# I2C-LLC_Mk_01.net
KiCad netlist of a schematic drawn in EAGLE
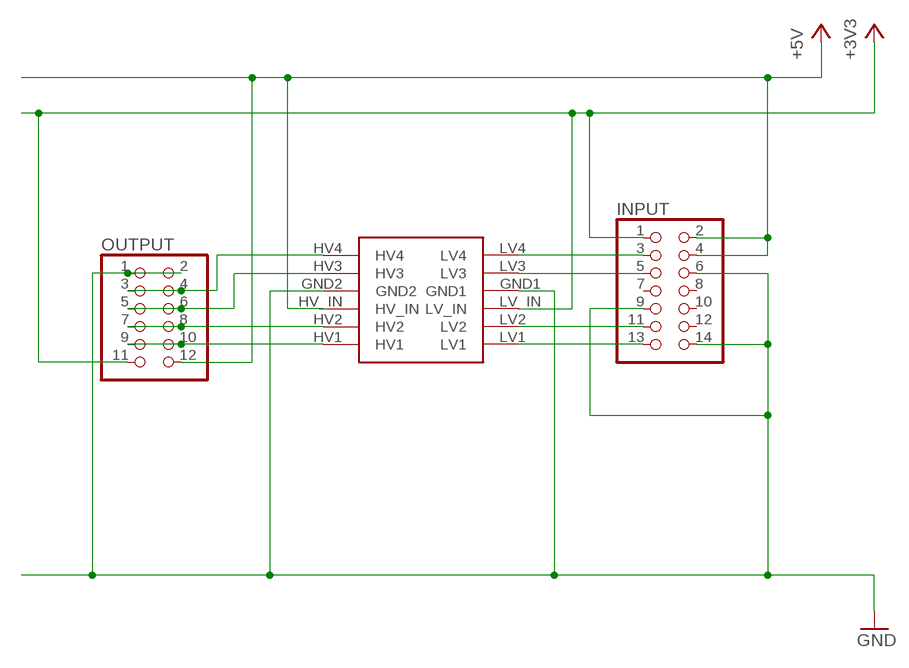
[diagram p0: schematic, sheet 1]

(export (version "E")
  (design (tool "Eeschema 10.0.6"))
  (components
    (comp (ref "INPUT")
      (value "PINHD-2X7")
      (footprint "eagle-import:2X07")
      (libsource (lib "eagle-import") (part "PINHD-2X7"))
    )
    (comp (ref "OUTPUT")
      (value "PINHD-2X6")
      (footprint "eagle-import:2X06")
      (libsource (lib "eagle-import") (part "PINHD-2X6"))
    )
    (comp (ref "U$1")
      (value "BD-LLC")
      (footprint "eagle-import:BD-LLC")
      (libsource (lib "eagle-import") (part "BD-LLC"))
    )
  )
  (nets
    (net (code "1") (name "+3V3") (class "Default")
      (node (ref "INPUT") (pin "1") (pinfunction "1_1") (pintype "passive"))
      (node (ref "OUTPUT") (pin "11") (pinfunction "11_11") (pintype "passive"))
      (node (ref "U$1") (pin "LV_IN") (pinfunction "LV_IN_LV_IN") (pintype "bidirectional"))
    )
    (net (code "2") (name "+5V") (class "Default")
      (node (ref "INPUT") (pin "2") (pinfunction "2_2") (pintype "passive"))
      (node (ref "INPUT") (pin "4") (pinfunction "4_4") (pintype "passive"))
      (node (ref "OUTPUT") (pin "12") (pinfunction "12_12") (pintype "passive"))
      (node (ref "U$1") (pin "HV_IN") (pinfunction "HV_IN_HV_IN") (pintype "bidirectional"))
    )
    (net (code "3") (name "GND") (class "Default")
      (node (ref "INPUT") (pin "14") (pinfunction "14_14") (pintype "passive"))
      (node (ref "INPUT") (pin "6") (pinfunction "6_6") (pintype "passive"))
      (node (ref "INPUT") (pin "9") (pinfunction "9_9") (pintype "passive"))
      (node (ref "OUTPUT") (pin "1") (pinfunction "1_1") (pintype "passive"))
      (node (ref "OUTPUT") (pin "2") (pinfunction "2_2") (pintype "passive"))
      (node (ref "U$1") (pin "GND1") (pinfunction "GND1_GND1") (pintype "bidirectional"))
      (node (ref "U$1") (pin "GND2") (pinfunction "GND2_GND2") (pintype "bidirectional"))
    )
    (net (code "4") (name "Net-(INPUT-Pad3)") (class "Default")
      (node (ref "INPUT") (pin "3") (pinfunction "3_3") (pintype "passive"))
      (node (ref "U$1") (pin "LV4") (pinfunction "LV4_LV4") (pintype "bidirectional"))
    )
    (net (code "5") (name "Net-(INPUT-Pad5)") (class "Default")
      (node (ref "INPUT") (pin "5") (pinfunction "5_5") (pintype "passive"))
      (node (ref "U$1") (pin "LV3") (pinfunction "LV3_LV3") (pintype "bidirectional"))
    )
    (net (code "6") (name "Net-(INPUT-Pad11)") (class "Default")
      (node (ref "INPUT") (pin "11") (pinfunction "11_11") (pintype "passive"))
      (node (ref "U$1") (pin "LV2") (pinfunction "LV2_LV2") (pintype "bidirectional"))
    )
    (net (code "7") (name "Net-(INPUT-Pad13)") (class "Default")
      (node (ref "INPUT") (pin "13") (pinfunction "13_13") (pintype "passive"))
      (node (ref "U$1") (pin "LV1") (pinfunction "LV1_LV1") (pintype "bidirectional"))
    )
    (net (code "8") (name "Net-(OUTPUT-Pad3)") (class "Default")
      (node (ref "OUTPUT") (pin "3") (pinfunction "3_3") (pintype "passive"))
      (node (ref "OUTPUT") (pin "4") (pinfunction "4_4") (pintype "passive"))
      (node (ref "U$1") (pin "HV4") (pinfunction "HV4_HV4") (pintype "bidirectional"))
    )
    (net (code "9") (name "Net-(OUTPUT-Pad5)") (class "Default")
      (node (ref "OUTPUT") (pin "5") (pinfunction "5_5") (pintype "passive"))
      (node (ref "OUTPUT") (pin "6") (pinfunction "6_6") (pintype "passive"))
      (node (ref "U$1") (pin "HV3") (pinfunction "HV3_HV3") (pintype "bidirectional"))
    )
    (net (code "10") (name "Net-(OUTPUT-Pad7)") (class "Default")
      (node (ref "OUTPUT") (pin "7") (pinfunction "7_7") (pintype "passive"))
      (node (ref "OUTPUT") (pin "8") (pinfunction "8_8") (pintype "passive"))
      (node (ref "U$1") (pin "HV2") (pinfunction "HV2_HV2") (pintype "bidirectional"))
    )
    (net (code "11") (name "Net-(OUTPUT-Pad10)") (class "Default")
      (node (ref "OUTPUT") (pin "10") (pinfunction "10_10") (pintype "passive"))
      (node (ref "OUTPUT") (pin "9") (pinfunction "9_9") (pintype "passive"))
      (node (ref "U$1") (pin "HV1") (pinfunction "HV1_HV1") (pintype "bidirectional"))
    )
    (net (code "12") (name "unconnected-(INPUT-Pad7)") (class "Default")
      (node (ref "INPUT") (pin "7") (pinfunction "7_7") (pintype "passive"))
    )
    (net (code "13") (name "unconnected-(INPUT-Pad8)") (class "Default")
      (node (ref "INPUT") (pin "8") (pinfunction "8_8") (pintype "passive"))
    )
    (net (code "14") (name "unconnected-(INPUT-Pad10)") (class "Default")
      (node (ref "INPUT") (pin "10") (pinfunction "10_10") (pintype "passive"))
    )
    (net (code "15") (name "unconnected-(INPUT-Pad12)") (class "Default")
      (node (ref "INPUT") (pin "12") (pinfunction "12_12") (pintype "passive"))
    )
  )
)
